# MINI_SAM_D51_002.net
KiCad netlist of a schematic drawn in EAGLE
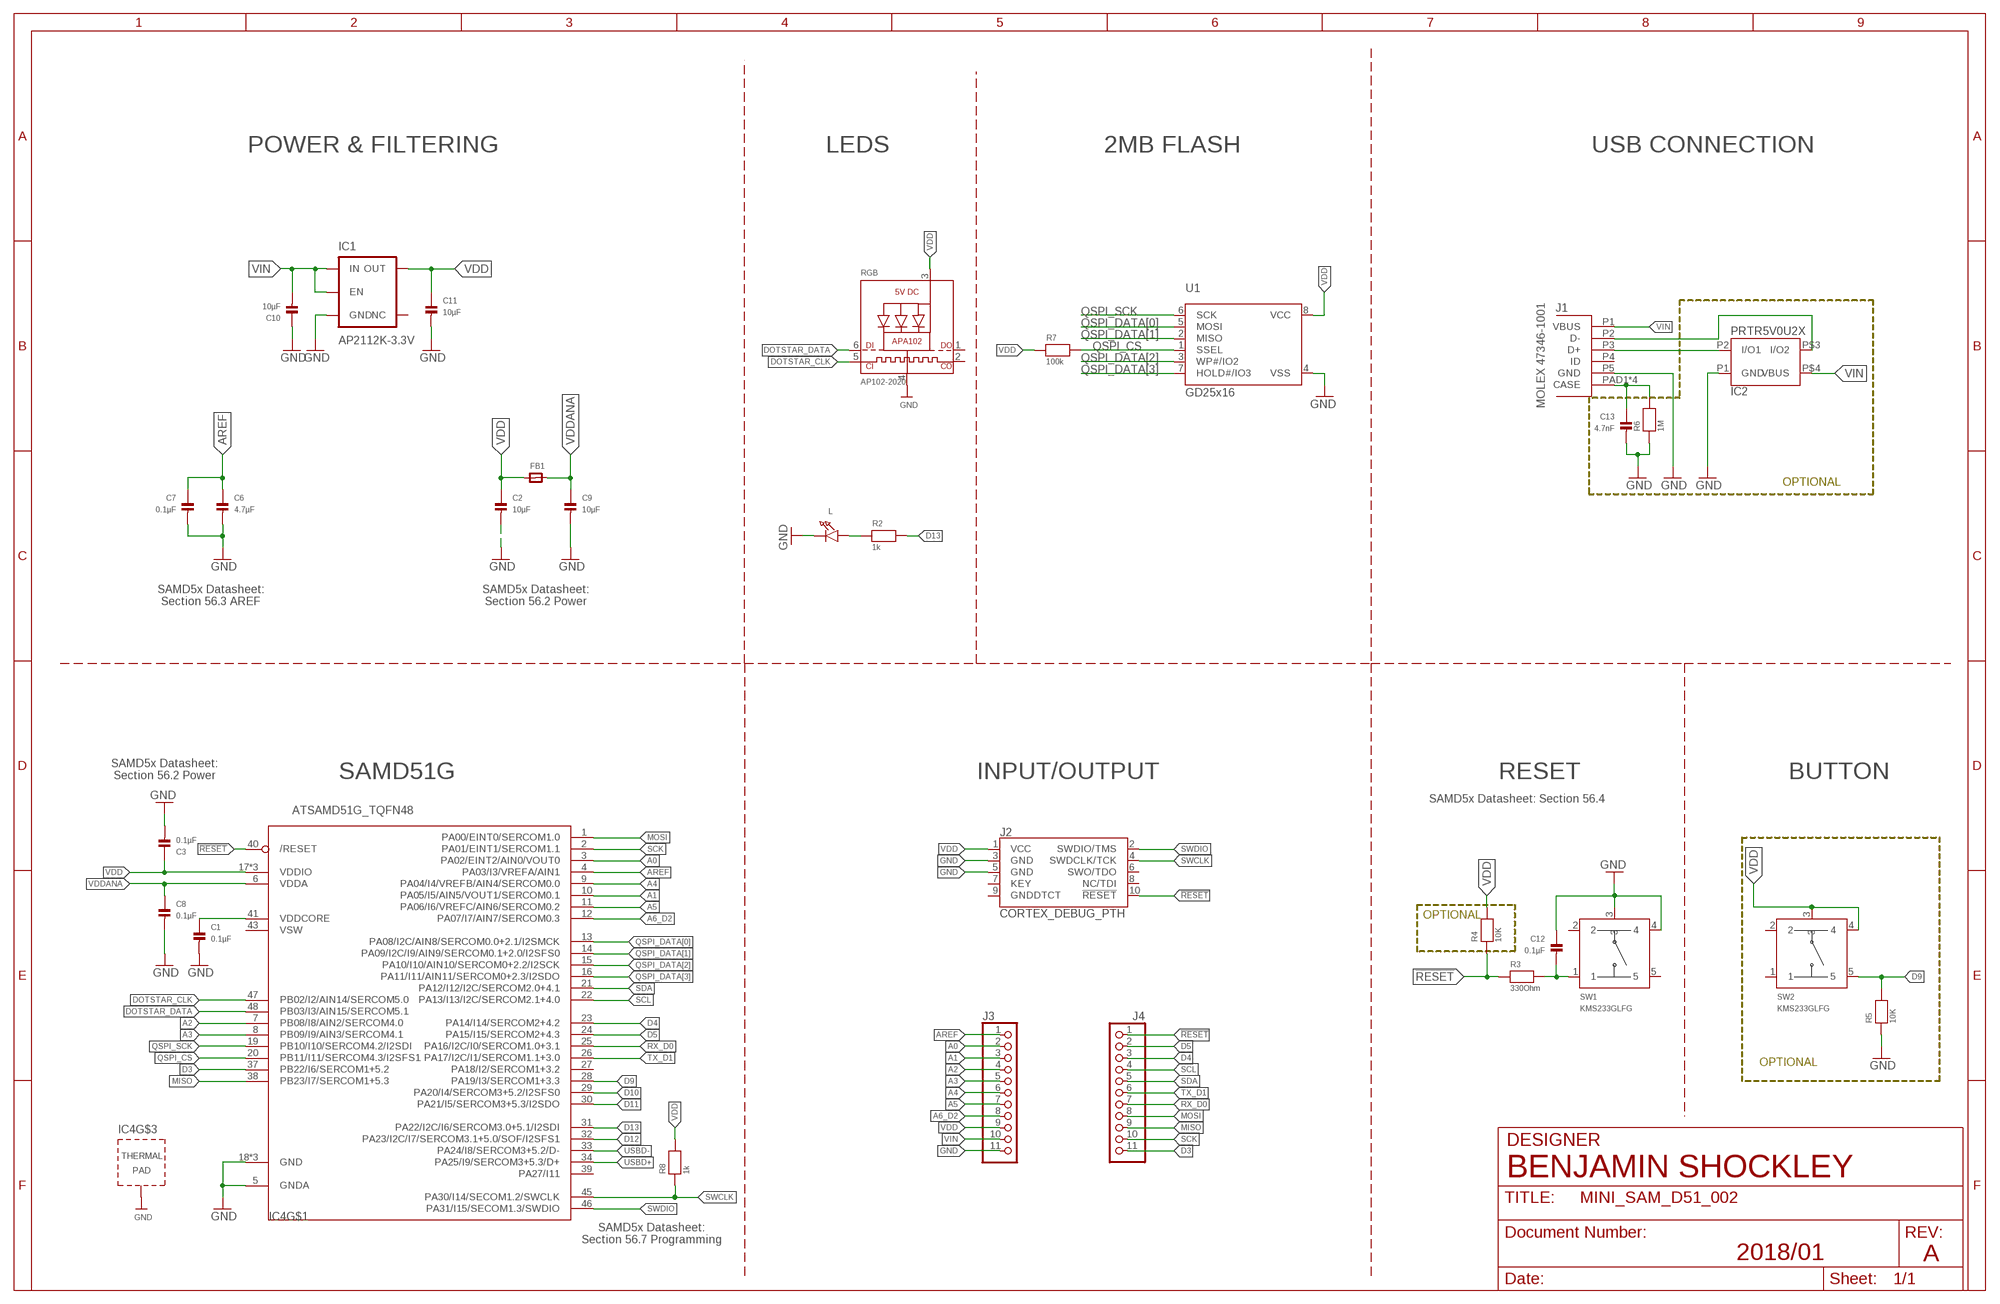
[diagram p0: schematic, sheet 1]

(export (version "E")
  (design (tool "Eeschema 10.0.6"))
  (components
    (comp (ref "C1")
      (value "0.1µF")
      (footprint "eagle-import:_0603MP")
      (libsource (lib "eagle-import") (part "CAP_CERAMIC_0603MP"))
    )
    (comp (ref "C2")
      (value "10µF")
      (footprint "eagle-import:_0603MP")
      (libsource (lib "eagle-import") (part "CAP_CERAMIC_0603MP"))
    )
    (comp (ref "C3")
      (value "0.1µF")
      (footprint "eagle-import:_0603MP")
      (libsource (lib "eagle-import") (part "CAP_CERAMIC_0603MP"))
    )
    (comp (ref "C6")
      (value "4.7µF")
      (footprint "eagle-import:_0603MP")
      (libsource (lib "eagle-import") (part "CAP_CERAMIC_0603MP"))
    )
    (comp (ref "C7")
      (value "0.1µF")
      (footprint "eagle-import:_0603MP")
      (libsource (lib "eagle-import") (part "CAP_CERAMIC_0603MP"))
    )
    (comp (ref "C8")
      (value "0.1µF")
      (footprint "eagle-import:_0603MP")
      (libsource (lib "eagle-import") (part "CAP_CERAMIC_0603MP"))
    )
    (comp (ref "C9")
      (value "10µF")
      (footprint "eagle-import:_0603MP")
      (libsource (lib "eagle-import") (part "CAP_CERAMIC_0603MP"))
    )
    (comp (ref "C10")
      (value "10µF")
      (footprint "eagle-import:_0603MP")
      (libsource (lib "eagle-import") (part "CAP_CERAMIC_0603MP"))
    )
    (comp (ref "C11")
      (value "10µF")
      (footprint "eagle-import:_0603MP")
      (libsource (lib "eagle-import") (part "CAP_CERAMIC_0603MP"))
    )
    (comp (ref "C12")
      (value "0.1µF")
      (footprint "eagle-import:_0603MP")
      (libsource (lib "eagle-import") (part "CAP_CERAMIC_0603MP"))
    )
    (comp (ref "C13")
      (value "4.7nF")
      (footprint "eagle-import:_0603MP")
      (libsource (lib "eagle-import") (part "CAP_CERAMIC_0603MP"))
    )
    (comp (ref "FB1")
      (value "FERRITE_0603MP")
      (footprint "eagle-import:_0603MP")
      (libsource (lib "eagle-import") (part "FERRITE_0603MP"))
    )
    (comp (ref "IC1")
      (value "AP2112K-3.3V")
      (footprint "eagle-import:SOT23-5")
      (libsource (lib "eagle-import") (part "V_REG_AP2112K-3.3V"))
    )
    (comp (ref "IC2")
      (value "PRTR5V0U2X")
      (footprint "eagle-import:SOT143B_REFLOW")
      (libsource (lib "eagle-import") (part "PRTR5V0U2X"))
    )
    (comp (ref "IC4")
      (value "ATSAMD51G_TQFN48")
      (footprint "eagle-import:TQFN48_7MM")
      (libsource (lib "eagle-import") (part "ATSAMD51G_TQFN48"))
    )
    (comp (ref "J1")
      (value "MOLEX_47346-100147346")
      (footprint "eagle-import:MOLEX_47346-1001")
      (libsource (lib "eagle-import") (part "MOLEX_47346-100147346"))
    )
    (comp (ref "J2")
      (value "CORTEX_DEBUG_PTH")
      (footprint "eagle-import:2X5-PTH-1.27MM")
      (libsource (lib "eagle-import") (part "CORTEX_DEBUG_PTH"))
    )
    (comp (ref "J3")
      (value "PINHD-1X111X11_SMT")
      (footprint "eagle-import:1X11_SMT")
      (libsource (lib "eagle-import") (part "PINHD-1X111X11_SMT"))
    )
    (comp (ref "J4")
      (value "PINHD-1X111X11_SMT")
      (footprint "eagle-import:1X11_SMT")
      (libsource (lib "eagle-import") (part "PINHD-1X111X11_SMT"))
    )
    (comp (ref "L")
      (value "LED0603_NOOUTLINE")
      (footprint "eagle-import:CHIPLED_0603_NOOUTLINE")
      (libsource (lib "eagle-import") (part "LED0603_NOOUTLINE"))
    )
    (comp (ref "R2")
      (value "1k")
      (footprint "eagle-import:_0603MP")
      (libsource (lib "eagle-import") (part "RESISTOR_0603MP"))
    )
    (comp (ref "R3")
      (value "330Ohm")
      (footprint "eagle-import:_0603MP")
      (libsource (lib "eagle-import") (part "RESISTOR_0603MP"))
    )
    (comp (ref "R4")
      (value "10K")
      (footprint "eagle-import:_0603MP")
      (libsource (lib "eagle-import") (part "RESISTOR_0603MP"))
    )
    (comp (ref "R5")
      (value "10K")
      (footprint "eagle-import:_0603MP")
      (libsource (lib "eagle-import") (part "RESISTOR_0603MP"))
    )
    (comp (ref "R6")
      (value "1M")
      (footprint "eagle-import:_0603MP")
      (libsource (lib "eagle-import") (part "RESISTOR_0603MP"))
    )
    (comp (ref "R7")
      (value "100k")
      (footprint "eagle-import:_0603MP")
      (libsource (lib "eagle-import") (part "RESISTOR_0603MP"))
    )
    (comp (ref "R8")
      (value "1k")
      (footprint "eagle-import:_0603MP")
      (libsource (lib "eagle-import") (part "RESISTOR_0603MP"))
    )
    (comp (ref "RGB")
      (value "AP102-2020")
      (footprint "eagle-import:APA102_2020")
      (libsource (lib "eagle-import") (part "APA1022020"))
    )
    (comp (ref "SW1")
      (value "KMS233GLFG")
      (footprint "eagle-import:KMS_SWITCH")
      (libsource (lib "eagle-import") (part "KMS_SWITCHKMS"))
    )
    (comp (ref "SW2")
      (value "KMS233GLFG")
      (footprint "eagle-import:KMS_SWITCH")
      (libsource (lib "eagle-import") (part "KMS_SWITCHKMS"))
    )
    (comp (ref "U1")
      (value "GD25x16")
      (footprint "eagle-import:USON8")
      (libsource (lib "eagle-import") (part "SPIFLASH_8PINUX"))
    )
  )
  (nets
    (net (code "1") (name "/VSW") (class "Default")
      (node (ref "IC4") (pin "43") (pinfunction "VSW_43") (pintype "power_in"))
    )
    (net (code "2") (name "/~{RESET}") (class "Default")
      (node (ref "IC4") (pin "40") (pinfunction "/RESET_40") (pintype "bidirectional"))
      (node (ref "J2") (pin "10") (pinfunction "~{RESET}_10") (pintype "bidirectional"))
      (node (ref "J4") (pin "1") (pinfunction "1_1") (pintype "passive"))
      (node (ref "R3") (pin "1") (pinfunction "1_1") (pintype "passive"))
      (node (ref "R4") (pin "1") (pinfunction "1_1") (pintype "passive"))
    )
    (net (code "3") (name "A0") (class "Default")
      (node (ref "IC4") (pin "3") (pinfunction "PA02/EINT2/AIN0/VOUT0_3") (pintype "bidirectional"))
      (node (ref "J3") (pin "2") (pinfunction "2_2") (pintype "passive"))
    )
    (net (code "4") (name "A1") (class "Default")
      (node (ref "IC4") (pin "10") (pinfunction "PA05/I5/AIN5/VOUT1/SERCOM0.1_10") (pintype "bidirectional"))
      (node (ref "J3") (pin "3") (pinfunction "3_3") (pintype "passive"))
    )
    (net (code "5") (name "A2") (class "Default")
      (node (ref "IC4") (pin "7") (pinfunction "PB08/I8/AIN2/SERCOM4.0_7") (pintype "bidirectional"))
      (node (ref "J3") (pin "4") (pinfunction "4_4") (pintype "passive"))
    )
    (net (code "6") (name "A3") (class "Default")
      (node (ref "IC4") (pin "8") (pinfunction "PB09/I9/AIN3/SERCOM4.1_8") (pintype "bidirectional"))
      (node (ref "J3") (pin "5") (pinfunction "5_5") (pintype "passive"))
    )
    (net (code "7") (name "A4") (class "Default")
      (node (ref "IC4") (pin "9") (pinfunction "PA04/I4/VREFB/AIN4/SERCOM0.0_9") (pintype "bidirectional"))
      (node (ref "J3") (pin "6") (pinfunction "6_6") (pintype "passive"))
    )
    (net (code "8") (name "A5") (class "Default")
      (node (ref "IC4") (pin "11") (pinfunction "PA06/I6/VREFC/AIN6/SERCOM0.2_11") (pintype "bidirectional"))
      (node (ref "J3") (pin "7") (pinfunction "7_7") (pintype "passive"))
    )
    (net (code "9") (name "A6_D2") (class "Default")
      (node (ref "IC4") (pin "12") (pinfunction "PA07/I7/AIN7/SERCOM0.3_12") (pintype "bidirectional"))
      (node (ref "J3") (pin "8") (pinfunction "8_8") (pintype "passive"))
    )
    (net (code "10") (name "AREF") (class "Default")
      (node (ref "C6") (pin "1") (pinfunction "P$1_1") (pintype "passive"))
      (node (ref "C7") (pin "1") (pinfunction "P$1_1") (pintype "passive"))
      (node (ref "IC4") (pin "4") (pinfunction "PA03/I3/VREFA/AIN1_4") (pintype "bidirectional"))
      (node (ref "J3") (pin "1") (pinfunction "1_1") (pintype "passive"))
    )
    (net (code "11") (name "D3") (class "Default")
      (node (ref "IC4") (pin "37") (pinfunction "PB22/I6/SERCOM1+5.2_37") (pintype "bidirectional"))
      (node (ref "J4") (pin "11") (pinfunction "11_11") (pintype "passive"))
    )
    (net (code "12") (name "D4") (class "Default")
      (node (ref "IC4") (pin "23") (pinfunction "PA14/I14/SERCOM2+4.2_23") (pintype "bidirectional"))
      (node (ref "J4") (pin "3") (pinfunction "3_3") (pintype "passive"))
    )
    (net (code "13") (name "D5") (class "Default")
      (node (ref "IC4") (pin "24") (pinfunction "PA15/I15/SERCOM2+4.3_24") (pintype "bidirectional"))
      (node (ref "J4") (pin "2") (pinfunction "2_2") (pintype "passive"))
    )
    (net (code "14") (name "D9") (class "Default")
      (node (ref "IC4") (pin "28") (pinfunction "PA19/I3/SERCOM1+3.3_28") (pintype "bidirectional"))
      (node (ref "R5") (pin "2") (pinfunction "2_2") (pintype "passive"))
      (node (ref "SW2") (pin "5") (pinfunction "5_5") (pintype "bidirectional"))
    )
    (net (code "15") (name "D10") (class "Default")
      (node (ref "IC4") (pin "29") (pinfunction "PA20/I4/SERCOM3+5.2/I2SFS0_29") (pintype "bidirectional"))
    )
    (net (code "16") (name "D11") (class "Default")
      (node (ref "IC4") (pin "30") (pinfunction "PA21/I5/SERCOM3+5.3/I2SDO_30") (pintype "bidirectional"))
    )
    (net (code "17") (name "D12") (class "Default")
      (node (ref "IC4") (pin "32") (pinfunction "PA23/I2C/I7/SERCOM3.1+5.0/SOF/I2SFS1_32") (pintype "bidirectional"))
    )
    (net (code "18") (name "D13") (class "Default")
      (node (ref "IC4") (pin "31") (pinfunction "PA22/I2C/I6/SERCOM3.0+5.1/I2SDI_31") (pintype "bidirectional"))
      (node (ref "R2") (pin "2") (pinfunction "2_2") (pintype "passive"))
    )
    (net (code "19") (name "DOTSTAR_CLK") (class "Default")
      (node (ref "IC4") (pin "47") (pinfunction "PB02/I2/AIN14/SERCOM5.0_47") (pintype "bidirectional"))
      (node (ref "RGB") (pin "5") (pinfunction "CKI_5") (pintype "input"))
    )
    (net (code "20") (name "DOTSTAR_DATA") (class "Default")
      (node (ref "IC4") (pin "48") (pinfunction "PB03/I3/AIN15/SERCOM5.1_48") (pintype "bidirectional"))
      (node (ref "RGB") (pin "6") (pinfunction "DI_6") (pintype "input"))
    )
    (net (code "21") (name "GND") (class "Default")
      (node (ref "C1") (pin "2") (pinfunction "P$2_2") (pintype "passive"))
      (node (ref "C10") (pin "1") (pinfunction "P$1_1") (pintype "passive"))
      (node (ref "C11") (pin "2") (pinfunction "P$2_2") (pintype "passive"))
      (node (ref "C12") (pin "1") (pinfunction "P$1_1") (pintype "passive"))
      (node (ref "C13") (pin "2") (pinfunction "P$2_2") (pintype "passive"))
      (node (ref "C2") (pin "2") (pinfunction "P$2_2") (pintype "passive"))
      (node (ref "C3") (pin "2") (pinfunction "P$2_2") (pintype "passive"))
      (node (ref "C6") (pin "2") (pinfunction "P$2_2") (pintype "passive"))
      (node (ref "C7") (pin "2") (pinfunction "P$2_2") (pintype "passive"))
      (node (ref "C8") (pin "2") (pinfunction "P$2_2") (pintype "passive"))
      (node (ref "C9") (pin "2") (pinfunction "P$2_2") (pintype "passive"))
      (node (ref "IC1") (pin "2") (pinfunction "GND_2") (pintype "input"))
      (node (ref "IC2") (pin "P1") (pinfunction "GND_P1") (pintype "bidirectional"))
      (node (ref "IC4") (pin "18") (pinfunction "GND_18") (pintype "power_in"))
      (node (ref "IC4") (pin "35") (pinfunction "GND_35") (pintype "power_in"))
      (node (ref "IC4") (pin "42") (pinfunction "GND_42") (pintype "power_in"))
      (node (ref "IC4") (pin "5") (pinfunction "GNDA_5") (pintype "power_in"))
      (node (ref "IC4") (pin "THERMAL") (pinfunction "TP_THERMAL") (pintype "power_in"))
      (node (ref "J1") (pin "P5") (pinfunction "GND_P5") (pintype "power_in"))
      (node (ref "J2") (pin "3") (pinfunction "GND_3") (pintype "bidirectional"))
      (node (ref "J2") (pin "5") (pinfunction "GND_5") (pintype "bidirectional"))
      (node (ref "J3") (pin "11") (pinfunction "11_11") (pintype "passive"))
      (node (ref "L") (pin "C") (pinfunction "C_C") (pintype "passive"))
      (node (ref "R5") (pin "1") (pinfunction "1_1") (pintype "passive"))
      (node (ref "R6") (pin "1") (pinfunction "1_1") (pintype "passive"))
      (node (ref "RGB") (pin "4") (pinfunction "GND_4") (pintype "power_in"))
      (node (ref "SW1") (pin "3") (pinfunction "3_3") (pintype "bidirectional"))
      (node (ref "SW1") (pin "4") (pinfunction "4_4") (pintype "bidirectional"))
      (node (ref "U1") (pin "4") (pinfunction "VSS_4") (pintype "bidirectional"))
    )
    (net (code "22") (name "MISO") (class "Default")
      (node (ref "IC4") (pin "38") (pinfunction "PB23/I7/SERCOM1+5.3_38") (pintype "bidirectional"))
      (node (ref "J4") (pin "9") (pinfunction "9_9") (pintype "passive"))
    )
    (net (code "23") (name "MOSI") (class "Default")
      (node (ref "IC4") (pin "1") (pinfunction "PA00/EINT0/SERCOM1.0_1") (pintype "bidirectional"))
      (node (ref "J4") (pin "8") (pinfunction "8_8") (pintype "passive"))
    )
    (net (code "24") (name "Net-(C1-P$1)") (class "Default")
      (node (ref "C1") (pin "1") (pinfunction "P$1_1") (pintype "passive"))
      (node (ref "IC4") (pin "41") (pinfunction "VDDCORE_41") (pintype "power_in"))
    )
    (net (code "25") (name "Net-(C12-P$2)") (class "Default")
      (node (ref "C12") (pin "2") (pinfunction "P$2_2") (pintype "passive"))
      (node (ref "R3") (pin "2") (pinfunction "2_2") (pintype "passive"))
      (node (ref "SW1") (pin "1") (pinfunction "1_1") (pintype "bidirectional"))
    )
    (net (code "26") (name "Net-(C13-P$1)") (class "Default")
      (node (ref "C13") (pin "1") (pinfunction "P$1_1") (pintype "passive"))
      (node (ref "J1") (pin "PAD1") (pinfunction "CASE_PAD1") (pintype "bidirectional"))
      (node (ref "J1") (pin "PAD2") (pinfunction "CASE_PAD2") (pintype "bidirectional"))
      (node (ref "J1") (pin "PAD3") (pinfunction "CASE_PAD3") (pintype "bidirectional"))
      (node (ref "J1") (pin "PAD4") (pinfunction "CASE_PAD4") (pintype "bidirectional"))
      (node (ref "R6") (pin "2") (pinfunction "2_2") (pintype "passive"))
    )
    (net (code "27") (name "Net-(L-PadA)") (class "Default")
      (node (ref "L") (pin "A") (pinfunction "A_A") (pintype "passive"))
      (node (ref "R2") (pin "1") (pinfunction "1_1") (pintype "passive"))
    )
    (net (code "28") (name "QSPI_CS") (class "Default")
      (node (ref "IC4") (pin "20") (pinfunction "PB11/I11/SERCOM4.3/I2SFS1_20") (pintype "bidirectional"))
      (node (ref "R7") (pin "2") (pinfunction "2_2") (pintype "passive"))
      (node (ref "U1") (pin "1") (pinfunction "SSEL_1") (pintype "bidirectional"))
    )
    (net (code "29") (name "QSPI_DATA[0]") (class "Default")
      (node (ref "IC4") (pin "13") (pinfunction "PA08/I2C/AIN8/SERCOM0.0+2.1/I2SMCK_13") (pintype "bidirectional"))
      (node (ref "U1") (pin "5") (pinfunction "MOSI_5") (pintype "bidirectional"))
    )
    (net (code "30") (name "QSPI_DATA[1]") (class "Default")
      (node (ref "IC4") (pin "14") (pinfunction "PA09/I2C/I9/AIN9/SERCOM0.1+2.0/I2SFS0_14") (pintype "bidirectional"))
      (node (ref "U1") (pin "2") (pinfunction "MISO_2") (pintype "bidirectional"))
    )
    (net (code "31") (name "QSPI_DATA[2]") (class "Default")
      (node (ref "IC4") (pin "15") (pinfunction "PA10/I10/AIN10/SERCOM0+2.2/I2SCK_15") (pintype "bidirectional"))
      (node (ref "U1") (pin "3") (pinfunction "WP#/IO2_3") (pintype "bidirectional"))
    )
    (net (code "32") (name "QSPI_DATA[3]") (class "Default")
      (node (ref "IC4") (pin "16") (pinfunction "PA11/I11/AIN11/SERCOM0+2.3/I2SDO_16") (pintype "bidirectional"))
      (node (ref "U1") (pin "7") (pinfunction "HOLD#/IO3_7") (pintype "bidirectional"))
    )
    (net (code "33") (name "QSPI_SCK") (class "Default")
      (node (ref "IC4") (pin "19") (pinfunction "PB10/I10/SERCOM4.2/I2SDI_19") (pintype "bidirectional"))
      (node (ref "U1") (pin "6") (pinfunction "SCK_6") (pintype "bidirectional"))
    )
    (net (code "34") (name "RX_D0") (class "Default")
      (node (ref "IC4") (pin "25") (pinfunction "PA16/I2C/I0/SERCOM1.0+3.1_25") (pintype "bidirectional"))
      (node (ref "J4") (pin "7") (pinfunction "7_7") (pintype "passive"))
    )
    (net (code "35") (name "SCK") (class "Default")
      (node (ref "IC4") (pin "2") (pinfunction "PA01/EINT1/SERCOM1.1_2") (pintype "bidirectional"))
      (node (ref "J4") (pin "10") (pinfunction "10_10") (pintype "passive"))
    )
    (net (code "36") (name "SCL") (class "Default")
      (node (ref "IC4") (pin "22") (pinfunction "PA13/I13/I2C/SERCOM2.1+4.0_22") (pintype "bidirectional"))
      (node (ref "J4") (pin "4") (pinfunction "4_4") (pintype "passive"))
    )
    (net (code "37") (name "SDA") (class "Default")
      (node (ref "IC4") (pin "21") (pinfunction "PA12/I12/I2C/SERCOM2.0+4.1_21") (pintype "bidirectional"))
      (node (ref "J4") (pin "5") (pinfunction "5_5") (pintype "passive"))
    )
    (net (code "38") (name "SWCLK") (class "Default")
      (node (ref "IC4") (pin "45") (pinfunction "PA30/I14/SECOM1.2/SWCLK_45") (pintype "bidirectional"))
      (node (ref "J2") (pin "4") (pinfunction "SWDCLK/TCK_4") (pintype "bidirectional"))
      (node (ref "R8") (pin "1") (pinfunction "1_1") (pintype "passive"))
    )
    (net (code "39") (name "SWDIO") (class "Default")
      (node (ref "IC4") (pin "46") (pinfunction "PA31/I15/SECOM1.3/SWDIO_46") (pintype "bidirectional"))
      (node (ref "J2") (pin "2") (pinfunction "SWDIO/TMS_2") (pintype "bidirectional"))
    )
    (net (code "40") (name "TX_D1") (class "Default")
      (node (ref "IC4") (pin "26") (pinfunction "PA17/I2C/I1/SERCOM1.1+3.0_26") (pintype "bidirectional"))
      (node (ref "J4") (pin "6") (pinfunction "6_6") (pintype "passive"))
    )
    (net (code "41") (name "USBD+") (class "Default")
      (node (ref "IC2") (pin "P2") (pinfunction "I/O1_P2") (pintype "bidirectional"))
      (node (ref "IC4") (pin "34") (pinfunction "PA25/I9/SERCOM3+5.3/D+_34") (pintype "bidirectional"))
      (node (ref "J1") (pin "P3") (pinfunction "D+_P3") (pintype "bidirectional"))
    )
    (net (code "42") (name "USBD-") (class "Default")
      (node (ref "IC2") (pin "P$3") (pinfunction "I/O2_P$3") (pintype "bidirectional"))
      (node (ref "IC4") (pin "33") (pinfunction "PA24/I8/SERCOM3+5.2/D-_33") (pintype "bidirectional"))
      (node (ref "J1") (pin "P2") (pinfunction "D-_P2") (pintype "bidirectional"))
    )
    (net (code "43") (name "VDD") (class "Default")
      (node (ref "C11") (pin "1") (pinfunction "P$1_1") (pintype "passive"))
      (node (ref "C2") (pin "1") (pinfunction "P$1_1") (pintype "passive"))
      (node (ref "C3") (pin "1") (pinfunction "P$1_1") (pintype "passive"))
      (node (ref "FB1") (pin "1") (pinfunction "P$1_1") (pintype "passive"))
      (node (ref "IC1") (pin "5") (pinfunction "OUT_5") (pintype "passive"))
      (node (ref "IC4") (pin "17") (pinfunction "VDDIO_17") (pintype "power_in"))
      (node (ref "IC4") (pin "36") (pinfunction "VDDIO_36") (pintype "power_in"))
      (node (ref "IC4") (pin "44") (pinfunction "VDDIO_44") (pintype "power_in"))
      (node (ref "J2") (pin "1") (pinfunction "VCC_1") (pintype "bidirectional"))
      (node (ref "J3") (pin "9") (pinfunction "9_9") (pintype "passive"))
      (node (ref "R4") (pin "2") (pinfunction "2_2") (pintype "passive"))
      (node (ref "R7") (pin "1") (pinfunction "1_1") (pintype "passive"))
      (node (ref "R8") (pin "2") (pinfunction "2_2") (pintype "passive"))
      (node (ref "RGB") (pin "3") (pinfunction "VDD_3") (pintype "power_in"))
      (node (ref "SW2") (pin "3") (pinfunction "3_3") (pintype "bidirectional"))
      (node (ref "SW2") (pin "4") (pinfunction "4_4") (pintype "bidirectional"))
      (node (ref "U1") (pin "8") (pinfunction "VCC_8") (pintype "bidirectional"))
    )
    (net (code "44") (name "VDDANA") (class "Default")
      (node (ref "C8") (pin "1") (pinfunction "P$1_1") (pintype "passive"))
      (node (ref "C9") (pin "1") (pinfunction "P$1_1") (pintype "passive"))
      (node (ref "FB1") (pin "2") (pinfunction "P$2_2") (pintype "passive"))
      (node (ref "IC4") (pin "6") (pinfunction "VDDA_6") (pintype "power_in"))
    )
    (net (code "45") (name "VIN") (class "Default")
      (node (ref "C10") (pin "2") (pinfunction "P$2_2") (pintype "passive"))
      (node (ref "IC1") (pin "1") (pinfunction "IN_1") (pintype "input"))
      (node (ref "IC1") (pin "3") (pinfunction "EN_3") (pintype "input"))
      (node (ref "IC2") (pin "P$4") (pinfunction "VBUS_P$4") (pintype "bidirectional"))
      (node (ref "J1") (pin "P1") (pinfunction "VBUS_P1") (pintype "power_in"))
      (node (ref "J3") (pin "10") (pinfunction "10_10") (pintype "passive"))
    )
    (net (code "46") (name "unconnected-(IC1-NC-Pad4)") (class "Default")
      (node (ref "IC1") (pin "4") (pinfunction "NC_4") (pintype "input"))
    )
    (net (code "47") (name "unconnected-(IC4A-PA18{slash}I2{slash}SERCOM1+3.2-Pad27)") (class "Default")
      (node (ref "IC4") (pin "27") (pinfunction "PA18/I2/SERCOM1+3.2_27") (pintype "bidirectional"))
    )
    (net (code "48") (name "unconnected-(IC4A-PA27{slash}I11-Pad39)") (class "Default")
      (node (ref "IC4") (pin "39") (pinfunction "PA27/I11_39") (pintype "bidirectional"))
    )
    (net (code "49") (name "unconnected-(J1-ID-PadP4)") (class "Default")
      (node (ref "J1") (pin "P4") (pinfunction "ID_P4") (pintype "bidirectional"))
    )
    (net (code "50") (name "unconnected-(J2-GNDDTCT-Pad9)") (class "Default")
      (node (ref "J2") (pin "9") (pinfunction "GNDDTCT_9") (pintype "bidirectional"))
    )
    (net (code "51") (name "unconnected-(J2-KEY-Pad7)") (class "Default")
      (node (ref "J2") (pin "7") (pinfunction "KEY_7") (pintype "bidirectional"))
    )
    (net (code "52") (name "unconnected-(J2-NC{slash}TDI-Pad8)") (class "Default")
      (node (ref "J2") (pin "8") (pinfunction "NC/TDI_8") (pintype "bidirectional"))
    )
    (net (code "53") (name "unconnected-(J2-SWO{slash}TDO-Pad6)") (class "Default")
      (node (ref "J2") (pin "6") (pinfunction "SWO/TDO_6") (pintype "bidirectional"))
    )
    (net (code "54") (name "unconnected-(RGB-CKO-Pad2)") (class "Default")
      (node (ref "RGB") (pin "2") (pinfunction "CKO_2") (pintype "output"))
    )
    (net (code "55") (name "unconnected-(RGB-DO-Pad1)") (class "Default")
      (node (ref "RGB") (pin "1") (pinfunction "DO_1") (pintype "output"))
    )
    (net (code "56") (name "unconnected-(SW1-Pad2)") (class "Default")
      (node (ref "SW1") (pin "2") (pinfunction "2_2") (pintype "bidirectional"))
    )
    (net (code "57") (name "unconnected-(SW1-Pad5)") (class "Default")
      (node (ref "SW1") (pin "5") (pinfunction "5_5") (pintype "bidirectional"))
    )
    (net (code "58") (name "unconnected-(SW2-Pad1)") (class "Default")
      (node (ref "SW2") (pin "1") (pinfunction "1_1") (pintype "bidirectional"))
    )
    (net (code "59") (name "unconnected-(SW2-Pad2)") (class "Default")
      (node (ref "SW2") (pin "2") (pinfunction "2_2") (pintype "bidirectional"))
    )
  )
)
